# pot.net
KiCad netlist of a schematic drawn in Altium Designer
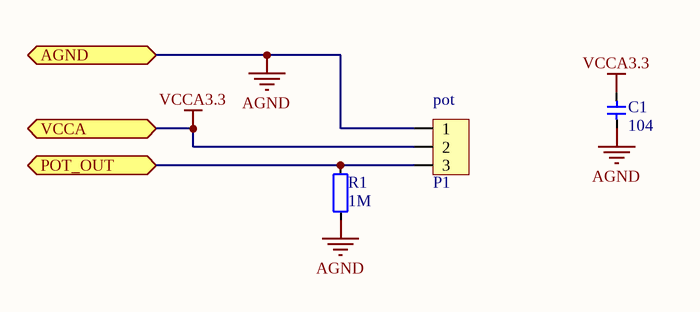
[diagram p0: pot.SchDoc]

(export (version "E")
  (design (tool "Eeschema 10.0.6"))
  (components
    (comp (ref "C1")
      (value "104")
      (footprint "PCB_PassiveCap:CAP_0603")
      (description "Capacitor")
      (fields (field (name "Comment") "Cap_0603"))
      (libsource (lib "SCH_Passive") (part "Cap_0603"))
    )
    (comp (ref "P1")
      (value "pot")
      (footprint "COMBICON PTSA 3")
      (description "Header")
      (libsource (lib "SCH_ConnectorHDR") (part "HDR1x3_2.54"))
    )
    (comp (ref "R1")
      (value "1M")
      (footprint "PCB_PassiveRes:RES_0603")
      (description "Resistor")
      (fields (field (name "Comment") "Res_0603"))
      (libsource (lib "SCH_Passive") (part "Res_0603"))
    )
  )
  (nets
    (net (code "1") (name "/POT_OUT") (class "Default")
      (node (ref "P1") (pin "3") (pinfunction "3_3") (pintype "passive"))
      (node (ref "R1") (pin "2") (pinfunction "2_2") (pintype "passive"))
    )
    (net (code "2") (name "AGND") (class "Default")
      (node (ref "C1") (pin "1") (pinfunction "1_1") (pintype "passive"))
      (node (ref "P1") (pin "1") (pinfunction "1_1") (pintype "passive"))
      (node (ref "R1") (pin "1") (pinfunction "1_1") (pintype "passive"))
    )
    (net (code "3") (name "VCCA3.3") (class "Default")
      (node (ref "C1") (pin "2") (pinfunction "2_2") (pintype "passive"))
      (node (ref "P1") (pin "2") (pinfunction "2_2") (pintype "passive"))
    )
  )
)
